# Zio_Qwiic_Soil_Moisture_Sensor.net
KiCad netlist of a schematic drawn in EAGLE
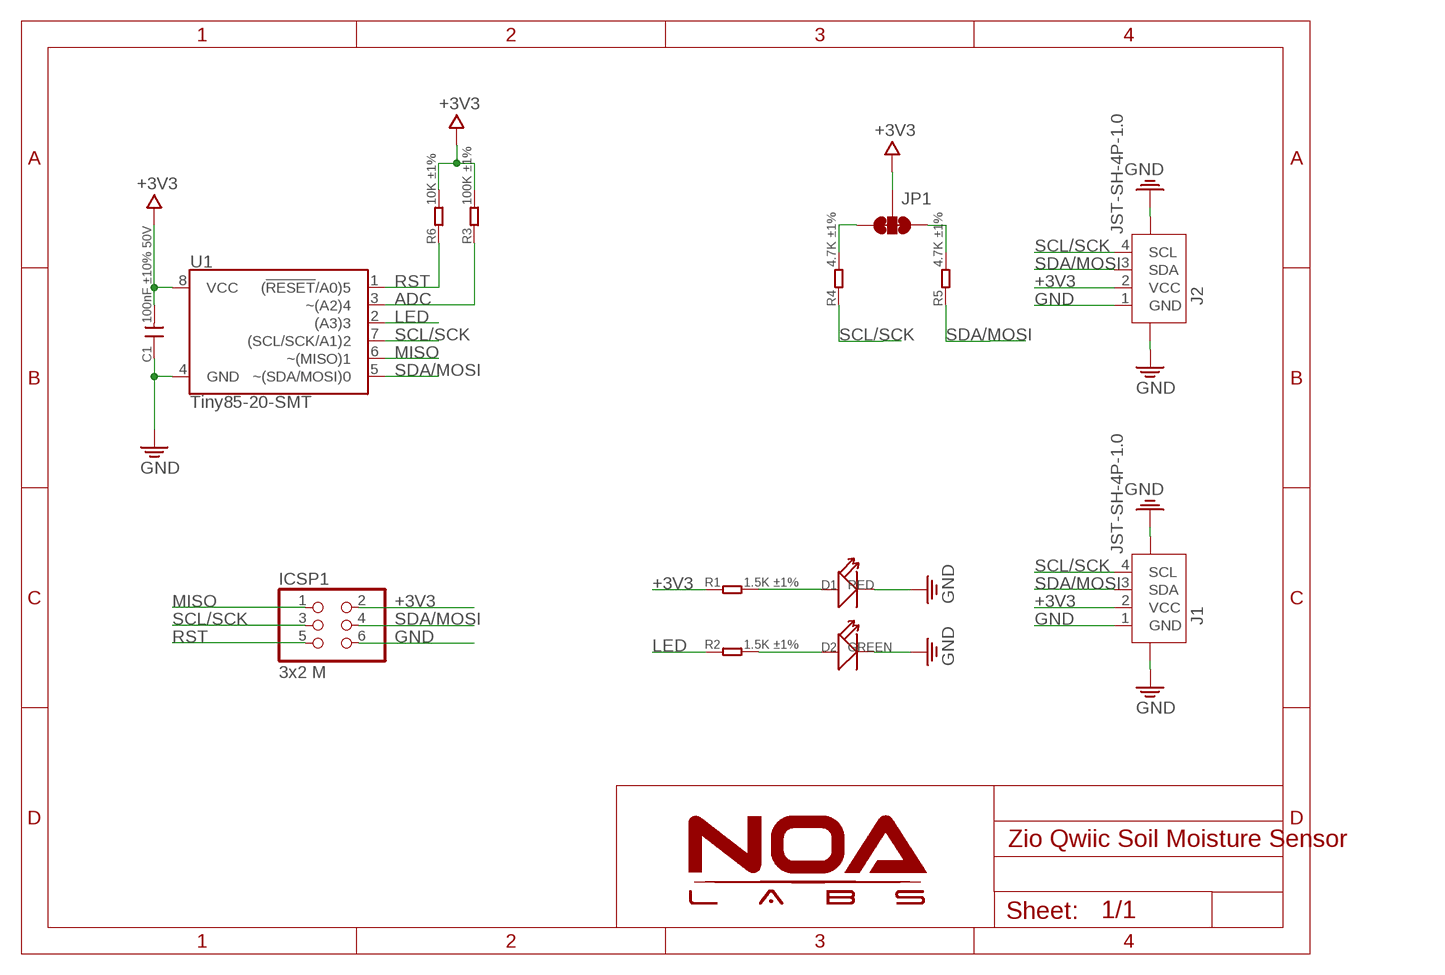
[diagram p0: schematic, sheet 1]

(export (version "E")
  (design (tool "Eeschema 10.0.6"))
  (components
    (comp (ref "C1")
      (value "100nF ±10% 50V")
      (footprint "eagle-import:C0603")
      (libsource (lib "eagle-import") (part "C-0603"))
    )
    (comp (ref "D1")
      (value "RED")
      (footprint "eagle-import:LED-0603")
      (libsource (lib "eagle-import") (part "LED'0603'"))
    )
    (comp (ref "D2")
      (value "GREEN")
      (footprint "eagle-import:LED-0603")
      (libsource (lib "eagle-import") (part "LED'0603'"))
    )
    (comp (ref "ICSP1")
      (value "3x2 M")
      (footprint "eagle-import:2X03")
      (libsource (lib "eagle-import") (part "PINHD-2X3"))
    )
    (comp (ref "J1")
      (value "JST-SH-4P-1.0")
      (footprint "eagle-import:JST-SH-4P")
      (libsource (lib "eagle-import") (part "JST-SH-4P-1.0"))
    )
    (comp (ref "J2")
      (value "JST-SH-4P-1.0")
      (footprint "eagle-import:JST-SH-4P")
      (libsource (lib "eagle-import") (part "JST-SH-4P-1.0"))
    )
    (comp (ref "JP1")
      (value "SMT-JUMPER_3_2-NC_TRACE")
      (footprint "eagle-import:SMT-JUMPER_3_2-NC_TRACE")
      (libsource (lib "eagle-import") (part "SMT-JUMPER_3_2-NC_TRACE"))
    )
    (comp (ref "R1")
      (value "1.5K ±1%")
      (footprint "eagle-import:R0603")
      (libsource (lib "eagle-import") (part "R-0603"))
    )
    (comp (ref "R2")
      (value "1.5K ±1%")
      (footprint "eagle-import:R0603")
      (libsource (lib "eagle-import") (part "R-0603"))
    )
    (comp (ref "R3")
      (value "100K ±1%")
      (footprint "eagle-import:R0603")
      (libsource (lib "eagle-import") (part "R-0603"))
    )
    (comp (ref "R4")
      (value "4.7K ±1%")
      (footprint "eagle-import:R0603")
      (libsource (lib "eagle-import") (part "R-0603"))
    )
    (comp (ref "R5")
      (value "4.7K ±1%")
      (footprint "eagle-import:R0603")
      (libsource (lib "eagle-import") (part "R-0603"))
    )
    (comp (ref "R6")
      (value "10K ±1%")
      (footprint "eagle-import:R0603")
      (libsource (lib "eagle-import") (part "R-0603"))
    )
    (comp (ref "U1")
      (value "Tiny85-20-SMT")
      (footprint "eagle-import:SO08-EIAJ_MCU")
      (libsource (lib "eagle-import") (part "ATTINY85-ARDUINOTINY85-20-SMT"))
    )
  )
  (nets
    (net (code "1") (name "+3V3") (class "Default")
      (node (ref "C1") (pin "2") (pinfunction "2_2") (pintype "passive"))
      (node (ref "ICSP1") (pin "2") (pinfunction "2_2") (pintype "passive"))
      (node (ref "J1") (pin "2") (pinfunction "VCC_2") (pintype "bidirectional"))
      (node (ref "J2") (pin "2") (pinfunction "VCC_2") (pintype "bidirectional"))
      (node (ref "JP1") (pin "2") (pinfunction "2_2") (pintype "passive"))
      (node (ref "R1") (pin "1") (pinfunction "1_1") (pintype "passive"))
      (node (ref "R3") (pin "2") (pinfunction "2_2") (pintype "passive"))
      (node (ref "R6") (pin "2") (pinfunction "2_2") (pintype "passive"))
      (node (ref "U1") (pin "8") (pinfunction "VCC_8") (pintype "bidirectional"))
    )
    (net (code "2") (name "/ADC") (class "Default")
      (node (ref "R3") (pin "1") (pinfunction "1_1") (pintype "passive"))
      (node (ref "U1") (pin "3") (pinfunction "~{(A2})4_3") (pintype "bidirectional"))
    )
    (net (code "3") (name "/LED") (class "Default")
      (node (ref "R2") (pin "1") (pinfunction "1_1") (pintype "passive"))
      (node (ref "U1") (pin "2") (pinfunction "(A3)3_2") (pintype "bidirectional"))
    )
    (net (code "4") (name "/MISO") (class "Default")
      (node (ref "ICSP1") (pin "1") (pinfunction "1_1") (pintype "passive"))
      (node (ref "U1") (pin "6") (pinfunction "~{(MISO})1_6") (pintype "bidirectional"))
    )
    (net (code "5") (name "/RST") (class "Default")
      (node (ref "ICSP1") (pin "5") (pinfunction "5_5") (pintype "passive"))
      (node (ref "R6") (pin "1") (pinfunction "1_1") (pintype "passive"))
      (node (ref "U1") (pin "1") (pinfunction "(~{RESET}/A0)5_1") (pintype "bidirectional"))
    )
    (net (code "6") (name "/SCL{slash}SCK") (class "Default")
      (node (ref "ICSP1") (pin "3") (pinfunction "3_3") (pintype "passive"))
      (node (ref "J1") (pin "4") (pinfunction "SCL_4") (pintype "bidirectional"))
      (node (ref "J2") (pin "4") (pinfunction "SCL_4") (pintype "bidirectional"))
      (node (ref "R4") (pin "1") (pinfunction "1_1") (pintype "passive"))
      (node (ref "U1") (pin "7") (pinfunction "(SCL/SCK/A1)2_7") (pintype "bidirectional"))
    )
    (net (code "7") (name "/SDA{slash}MOSI") (class "Default")
      (node (ref "ICSP1") (pin "4") (pinfunction "4_4") (pintype "passive"))
      (node (ref "J1") (pin "3") (pinfunction "SDA_3") (pintype "bidirectional"))
      (node (ref "J2") (pin "3") (pinfunction "SDA_3") (pintype "bidirectional"))
      (node (ref "R5") (pin "1") (pinfunction "1_1") (pintype "passive"))
      (node (ref "U1") (pin "5") (pinfunction "~{(SDA/MOSI})0_5") (pintype "bidirectional"))
    )
    (net (code "8") (name "GND") (class "Default")
      (node (ref "C1") (pin "1") (pinfunction "1_1") (pintype "passive"))
      (node (ref "D1") (pin "-") (pinfunction "-_-") (pintype "passive"))
      (node (ref "D2") (pin "-") (pinfunction "-_-") (pintype "passive"))
      (node (ref "ICSP1") (pin "6") (pinfunction "6_6") (pintype "passive"))
      (node (ref "J1") (pin "1") (pinfunction "GND_1") (pintype "bidirectional"))
      (node (ref "J1") (pin "NC1") (pinfunction "5_NC1") (pintype "bidirectional"))
      (node (ref "J1") (pin "NC2") (pinfunction "6_NC2") (pintype "bidirectional"))
      (node (ref "J2") (pin "1") (pinfunction "GND_1") (pintype "bidirectional"))
      (node (ref "J2") (pin "NC1") (pinfunction "5_NC1") (pintype "bidirectional"))
      (node (ref "J2") (pin "NC2") (pinfunction "6_NC2") (pintype "bidirectional"))
      (node (ref "U1") (pin "4") (pinfunction "GND_4") (pintype "bidirectional"))
    )
    (net (code "9") (name "Net-(D1-Pad+)") (class "Default")
      (node (ref "D1") (pin "+") (pinfunction "+_+") (pintype "passive"))
      (node (ref "R1") (pin "2") (pinfunction "2_2") (pintype "passive"))
    )
    (net (code "10") (name "Net-(D2-Pad+)") (class "Default")
      (node (ref "D2") (pin "+") (pinfunction "+_+") (pintype "passive"))
      (node (ref "R2") (pin "2") (pinfunction "2_2") (pintype "passive"))
    )
    (net (code "11") (name "Net-(JP1-Pad1)") (class "Default")
      (node (ref "JP1") (pin "1") (pinfunction "1_1") (pintype "passive"))
      (node (ref "R5") (pin "2") (pinfunction "2_2") (pintype "passive"))
    )
    (net (code "12") (name "Net-(JP1-Pad3)") (class "Default")
      (node (ref "JP1") (pin "3") (pinfunction "3_3") (pintype "passive"))
      (node (ref "R4") (pin "2") (pinfunction "2_2") (pintype "passive"))
    )
  )
)
